# CrystalBall.net
KiCad netlist of a schematic drawn in EAGLE
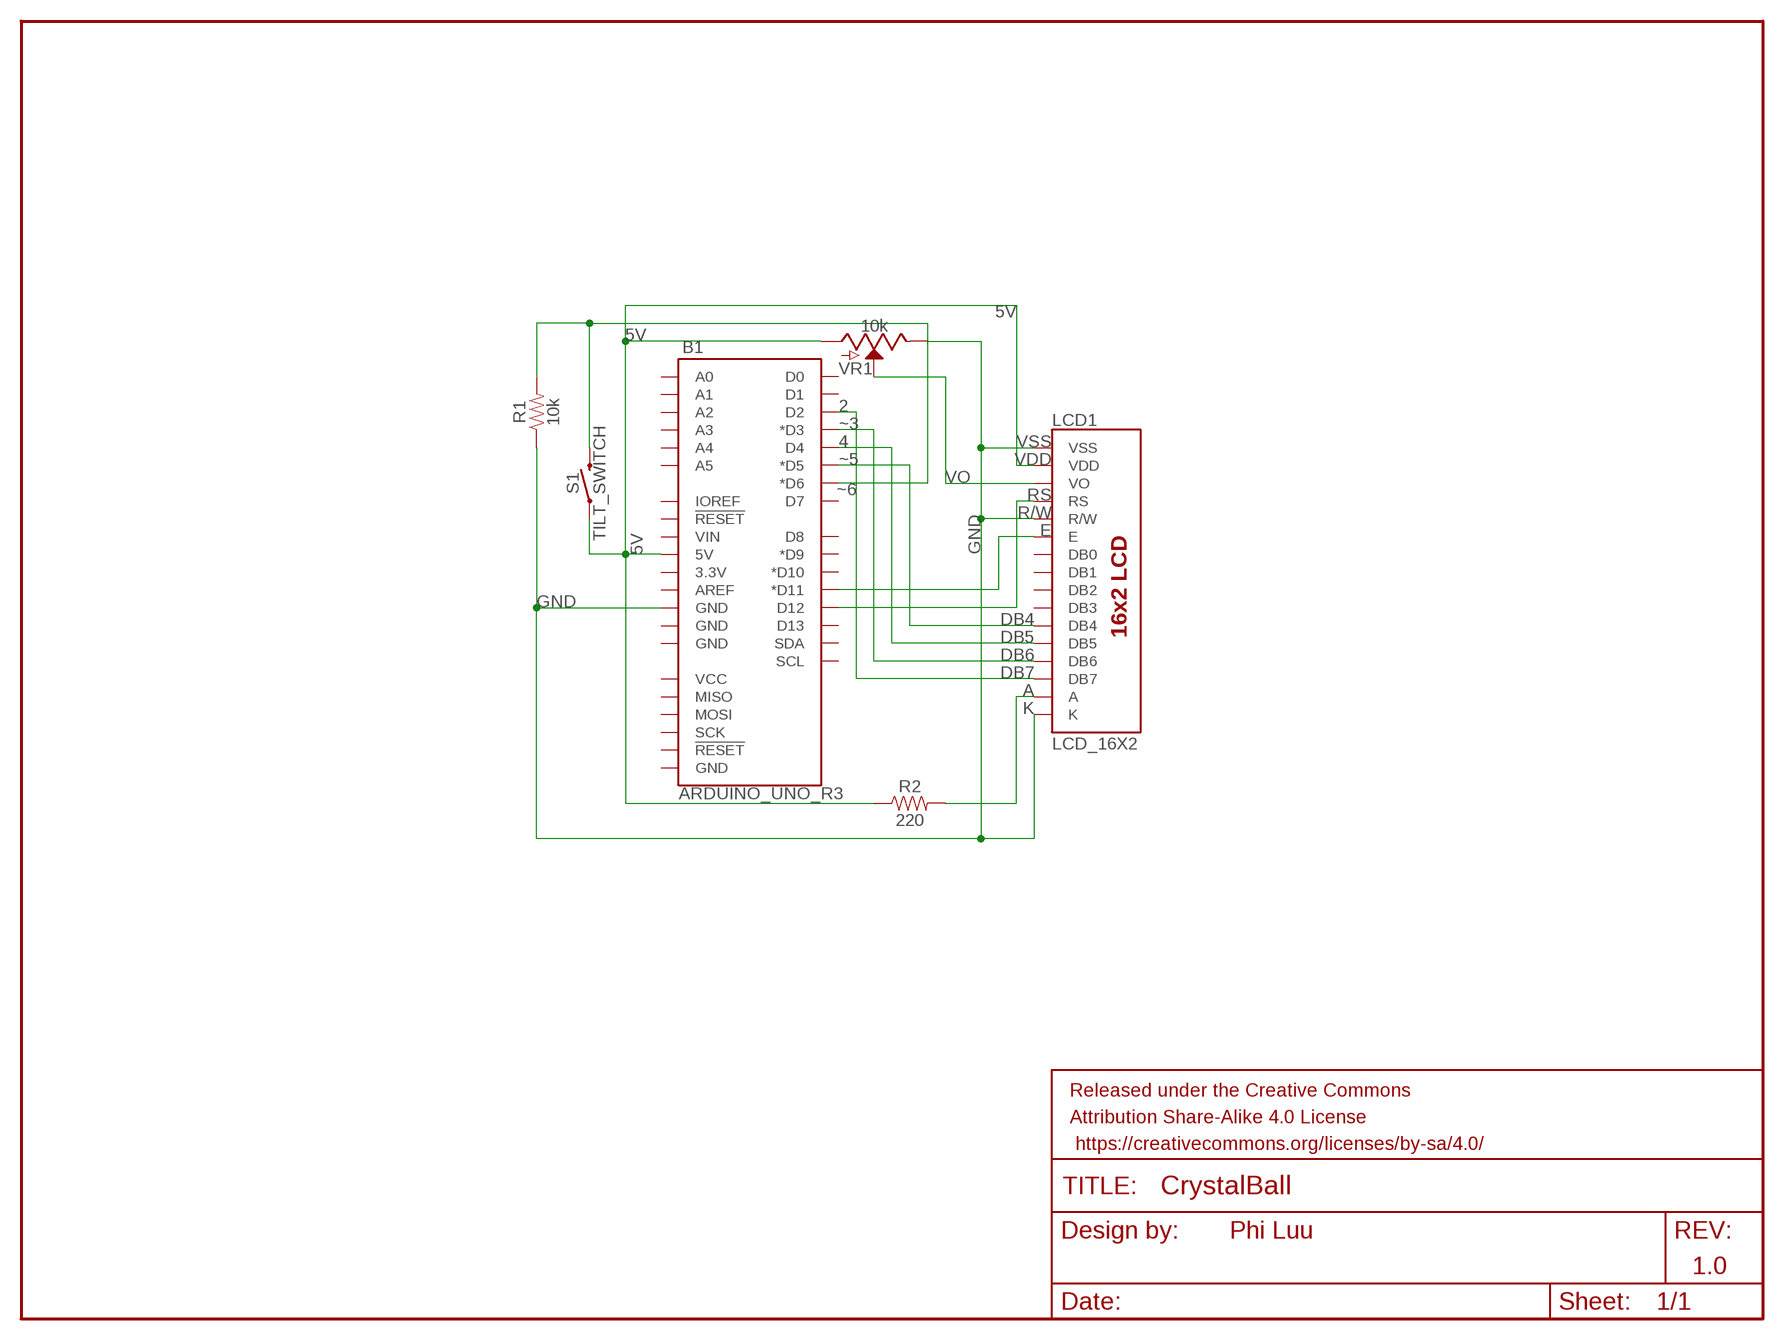
[diagram p0: schematic, sheet 1]

(export (version "E")
  (design (tool "Eeschema 10.0.6"))
  (components
    (comp (ref "B1")
      (value "ARDUINO_UNO_R3")
      (footprint "eagle-import:ARDUINO_R3")
      (libsource (lib "eagle-import") (part "ARDUINO_UNO_R3"))
    )
    (comp (ref "FRAME1")
      (value "FRAME-LETTER")
      (footprint "eagle-import:CREATIVE_COMMONS")
      (libsource (lib "eagle-import") (part "FRAME-LETTER"))
    )
    (comp (ref "LCD1")
      (value "LCD_16X2")
      (footprint "eagle-import:LCD-16X2")
      (libsource (lib "eagle-import") (part "LCD-16X2SILK"))
    )
    (comp (ref "R1")
      (value "10k")
      (footprint "eagle-import:AXIAL-0.3")
      (libsource (lib "eagle-import") (part "10KOHM-HORIZ-1/4W-5%"))
    )
    (comp (ref "R2")
      (value "220")
      (footprint "eagle-import:AXIAL-0.3")
      (libsource (lib "eagle-import") (part "10KOHM-HORIZ-1/4W-5%"))
    )
    (comp (ref "S1")
      (value "TILT_SWITCH")
      (footprint "eagle-import:TACTILE_SWITCH_PTH_6.0MM")
      (libsource (lib "eagle-import") (part "MOMENTARY-SWITCH-SPST-PTH-6.0MM"))
    )
    (comp (ref "VR1")
      (value "10k")
      (footprint "eagle-import:POT-PTH-ALPS")
      (libsource (lib "eagle-import") (part "POTENTIOMETER-PTH-9MM-1/20W-20%"))
    )
  )
  (nets
    (net (code "1") (name "/2") (class "Default")
      (node (ref "B1") (pin "D2") (pinfunction "D2_D2") (pintype "bidirectional"))
      (node (ref "LCD1") (pin "14") (pinfunction "DB7_14") (pintype "bidirectional"))
    )
    (net (code "2") (name "/4") (class "Default")
      (node (ref "B1") (pin "D4") (pinfunction "D4_D4") (pintype "bidirectional"))
      (node (ref "LCD1") (pin "12") (pinfunction "DB5_12") (pintype "bidirectional"))
    )
    (net (code "3") (name "/5V") (class "Default")
      (node (ref "B1") (pin "5V") (pinfunction "5V_5V") (pintype "bidirectional"))
      (node (ref "LCD1") (pin "2") (pinfunction "VDD_2") (pintype "power_in"))
      (node (ref "R2") (pin "P$1") (pinfunction "1_P$1") (pintype "passive"))
      (node (ref "S1") (pin "1") (pinfunction "1_1") (pintype "passive"))
      (node (ref "VR1") (pin "P$3") (pinfunction "A_P$3") (pintype "passive"))
    )
    (net (code "4") (name "/GND") (class "Default")
      (node (ref "B1") (pin "GND@4") (pinfunction "GND_GND@4") (pintype "bidirectional"))
      (node (ref "LCD1") (pin "1") (pinfunction "VSS_1") (pintype "power_in"))
      (node (ref "LCD1") (pin "16") (pinfunction "K_16") (pintype "power_in"))
      (node (ref "LCD1") (pin "5") (pinfunction "R/W_5") (pintype "input"))
      (node (ref "R1") (pin "P$1") (pinfunction "1_P$1") (pintype "passive"))
      (node (ref "VR1") (pin "P$1") (pinfunction "E_P$1") (pintype "passive"))
    )
    (net (code "5") (name "/~{3}") (class "Default")
      (node (ref "B1") (pin "D3") (pinfunction "*D3_D3") (pintype "bidirectional"))
      (node (ref "LCD1") (pin "13") (pinfunction "DB6_13") (pintype "bidirectional"))
    )
    (net (code "6") (name "/~{5}") (class "Default")
      (node (ref "B1") (pin "D5") (pinfunction "*D5_D5") (pintype "bidirectional"))
      (node (ref "LCD1") (pin "11") (pinfunction "DB4_11") (pintype "bidirectional"))
    )
    (net (code "7") (name "/~{6}") (class "Default")
      (node (ref "B1") (pin "D6") (pinfunction "*D6_D6") (pintype "bidirectional"))
      (node (ref "R1") (pin "P$2") (pinfunction "2_P$2") (pintype "passive"))
      (node (ref "S1") (pin "3") (pinfunction "2_3") (pintype "passive"))
    )
    (net (code "8") (name "Net-(B1-*D11)") (class "Default")
      (node (ref "B1") (pin "D11") (pinfunction "*D11_D11") (pintype "bidirectional"))
      (node (ref "LCD1") (pin "6") (pinfunction "E_6") (pintype "input"))
    )
    (net (code "9") (name "Net-(LCD1-A)") (class "Default")
      (node (ref "LCD1") (pin "15") (pinfunction "A_15") (pintype "power_in"))
      (node (ref "R2") (pin "P$2") (pinfunction "2_P$2") (pintype "passive"))
    )
    (net (code "10") (name "Net-(LCD1-RS)") (class "Default")
      (node (ref "B1") (pin "D12") (pinfunction "D12_D12") (pintype "bidirectional"))
      (node (ref "LCD1") (pin "4") (pinfunction "RS_4") (pintype "input"))
    )
    (net (code "11") (name "Net-(LCD1-VO)") (class "Default")
      (node (ref "LCD1") (pin "3") (pinfunction "VO_3") (pintype "bidirectional"))
      (node (ref "VR1") (pin "P$2") (pinfunction "S_P$2") (pintype "passive"))
    )
    (net (code "12") (name "unconnected-(B1-*D9-PadD9)") (class "Default")
      (node (ref "B1") (pin "D9") (pinfunction "*D9_D9") (pintype "bidirectional"))
    )
    (net (code "13") (name "unconnected-(B1-*D10-PadD10)") (class "Default")
      (node (ref "B1") (pin "D10") (pinfunction "*D10_D10") (pintype "bidirectional"))
    )
    (net (code "14") (name "unconnected-(B1-GND-PadGND@1)") (class "Default")
      (node (ref "B1") (pin "GND@1") (pinfunction "GND_GND@1") (pintype "bidirectional"))
    )
    (net (code "15") (name "unconnected-(B1-GND-PadGND@2)") (class "Default")
      (node (ref "B1") (pin "GND@2") (pinfunction "GND_GND@2") (pintype "bidirectional"))
    )
    (net (code "16") (name "unconnected-(B1-GND-PadGND@3)") (class "Default")
      (node (ref "B1") (pin "GND@3") (pinfunction "GND_GND@3") (pintype "bidirectional"))
    )
    (net (code "17") (name "unconnected-(B1-Pad3.3V)") (class "Default")
      (node (ref "B1") (pin "3.3V") (pinfunction "3.3V_3.3V") (pintype "bidirectional"))
    )
    (net (code "18") (name "unconnected-(B1-PadA0)") (class "Default")
      (node (ref "B1") (pin "A0") (pinfunction "A0_A0") (pintype "bidirectional"))
    )
    (net (code "19") (name "unconnected-(B1-PadA1)") (class "Default")
      (node (ref "B1") (pin "A1") (pinfunction "A1_A1") (pintype "bidirectional"))
    )
    (net (code "20") (name "unconnected-(B1-PadA2)") (class "Default")
      (node (ref "B1") (pin "A2") (pinfunction "A2_A2") (pintype "bidirectional"))
    )
    (net (code "21") (name "unconnected-(B1-PadA3)") (class "Default")
      (node (ref "B1") (pin "A3") (pinfunction "A3_A3") (pintype "bidirectional"))
    )
    (net (code "22") (name "unconnected-(B1-PadA4)") (class "Default")
      (node (ref "B1") (pin "A4") (pinfunction "A4_A4") (pintype "bidirectional"))
    )
    (net (code "23") (name "unconnected-(B1-PadA5)") (class "Default")
      (node (ref "B1") (pin "A5") (pinfunction "A5_A5") (pintype "bidirectional"))
    )
    (net (code "24") (name "unconnected-(B1-PadAREF)") (class "Default")
      (node (ref "B1") (pin "AREF") (pinfunction "AREF_AREF") (pintype "bidirectional"))
    )
    (net (code "25") (name "unconnected-(B1-PadD0)") (class "Default")
      (node (ref "B1") (pin "D0") (pinfunction "D0_D0") (pintype "bidirectional"))
    )
    (net (code "26") (name "unconnected-(B1-PadD1)") (class "Default")
      (node (ref "B1") (pin "D1") (pinfunction "D1_D1") (pintype "bidirectional"))
    )
    (net (code "27") (name "unconnected-(B1-PadD7)") (class "Default")
      (node (ref "B1") (pin "D7") (pinfunction "D7_D7") (pintype "bidirectional"))
    )
    (net (code "28") (name "unconnected-(B1-PadD8)") (class "Default")
      (node (ref "B1") (pin "D8") (pinfunction "D8_D8") (pintype "bidirectional"))
    )
    (net (code "29") (name "unconnected-(B1-PadD13)") (class "Default")
      (node (ref "B1") (pin "D13") (pinfunction "D13_D13") (pintype "bidirectional"))
    )
    (net (code "30") (name "unconnected-(B1-PadIOREF)") (class "Default")
      (node (ref "B1") (pin "IOREF") (pinfunction "IOREF_IOREF") (pintype "bidirectional"))
    )
    (net (code "31") (name "unconnected-(B1-PadMISO)") (class "Default")
      (node (ref "B1") (pin "MISO") (pinfunction "MISO_MISO") (pintype "bidirectional"))
    )
    (net (code "32") (name "unconnected-(B1-PadMOSI)") (class "Default")
      (node (ref "B1") (pin "MOSI") (pinfunction "MOSI_MOSI") (pintype "bidirectional"))
    )
    (net (code "33") (name "unconnected-(B1-PadSCK)") (class "Default")
      (node (ref "B1") (pin "SCK") (pinfunction "SCK_SCK") (pintype "bidirectional"))
    )
    (net (code "34") (name "unconnected-(B1-PadSCL)") (class "Default")
      (node (ref "B1") (pin "SCL") (pinfunction "SCL_SCL") (pintype "bidirectional"))
    )
    (net (code "35") (name "unconnected-(B1-PadSDA)") (class "Default")
      (node (ref "B1") (pin "SDA") (pinfunction "SDA_SDA") (pintype "bidirectional"))
    )
    (net (code "36") (name "unconnected-(B1-PadVCC)") (class "Default")
      (node (ref "B1") (pin "VCC") (pinfunction "VCC_VCC") (pintype "bidirectional"))
    )
    (net (code "37") (name "unconnected-(B1-PadVIN)") (class "Default")
      (node (ref "B1") (pin "VIN") (pinfunction "VIN_VIN") (pintype "bidirectional"))
    )
    (net (code "38") (name "unconnected-(B1-~{RESET}-PadRESET@1)") (class "Default")
      (node (ref "B1") (pin "RESET@1") (pinfunction "~{RESET}_RESET@1") (pintype "bidirectional"))
    )
    (net (code "39") (name "unconnected-(B1-~{RESET}-PadRESET@2)") (class "Default")
      (node (ref "B1") (pin "RESET@2") (pinfunction "~{RESET}_RESET@2") (pintype "bidirectional"))
    )
    (net (code "40") (name "unconnected-(LCD1-DB0-Pad7)") (class "Default")
      (node (ref "LCD1") (pin "7") (pinfunction "DB0_7") (pintype "bidirectional"))
    )
    (net (code "41") (name "unconnected-(LCD1-DB1-Pad8)") (class "Default")
      (node (ref "LCD1") (pin "8") (pinfunction "DB1_8") (pintype "bidirectional"))
    )
    (net (code "42") (name "unconnected-(LCD1-DB2-Pad9)") (class "Default")
      (node (ref "LCD1") (pin "9") (pinfunction "DB2_9") (pintype "bidirectional"))
    )
    (net (code "43") (name "unconnected-(LCD1-DB3-Pad10)") (class "Default")
      (node (ref "LCD1") (pin "10") (pinfunction "DB3_10") (pintype "bidirectional"))
    )
  )
)
